# design.net
KiCad netlist of a schematic drawn in Altium Designer
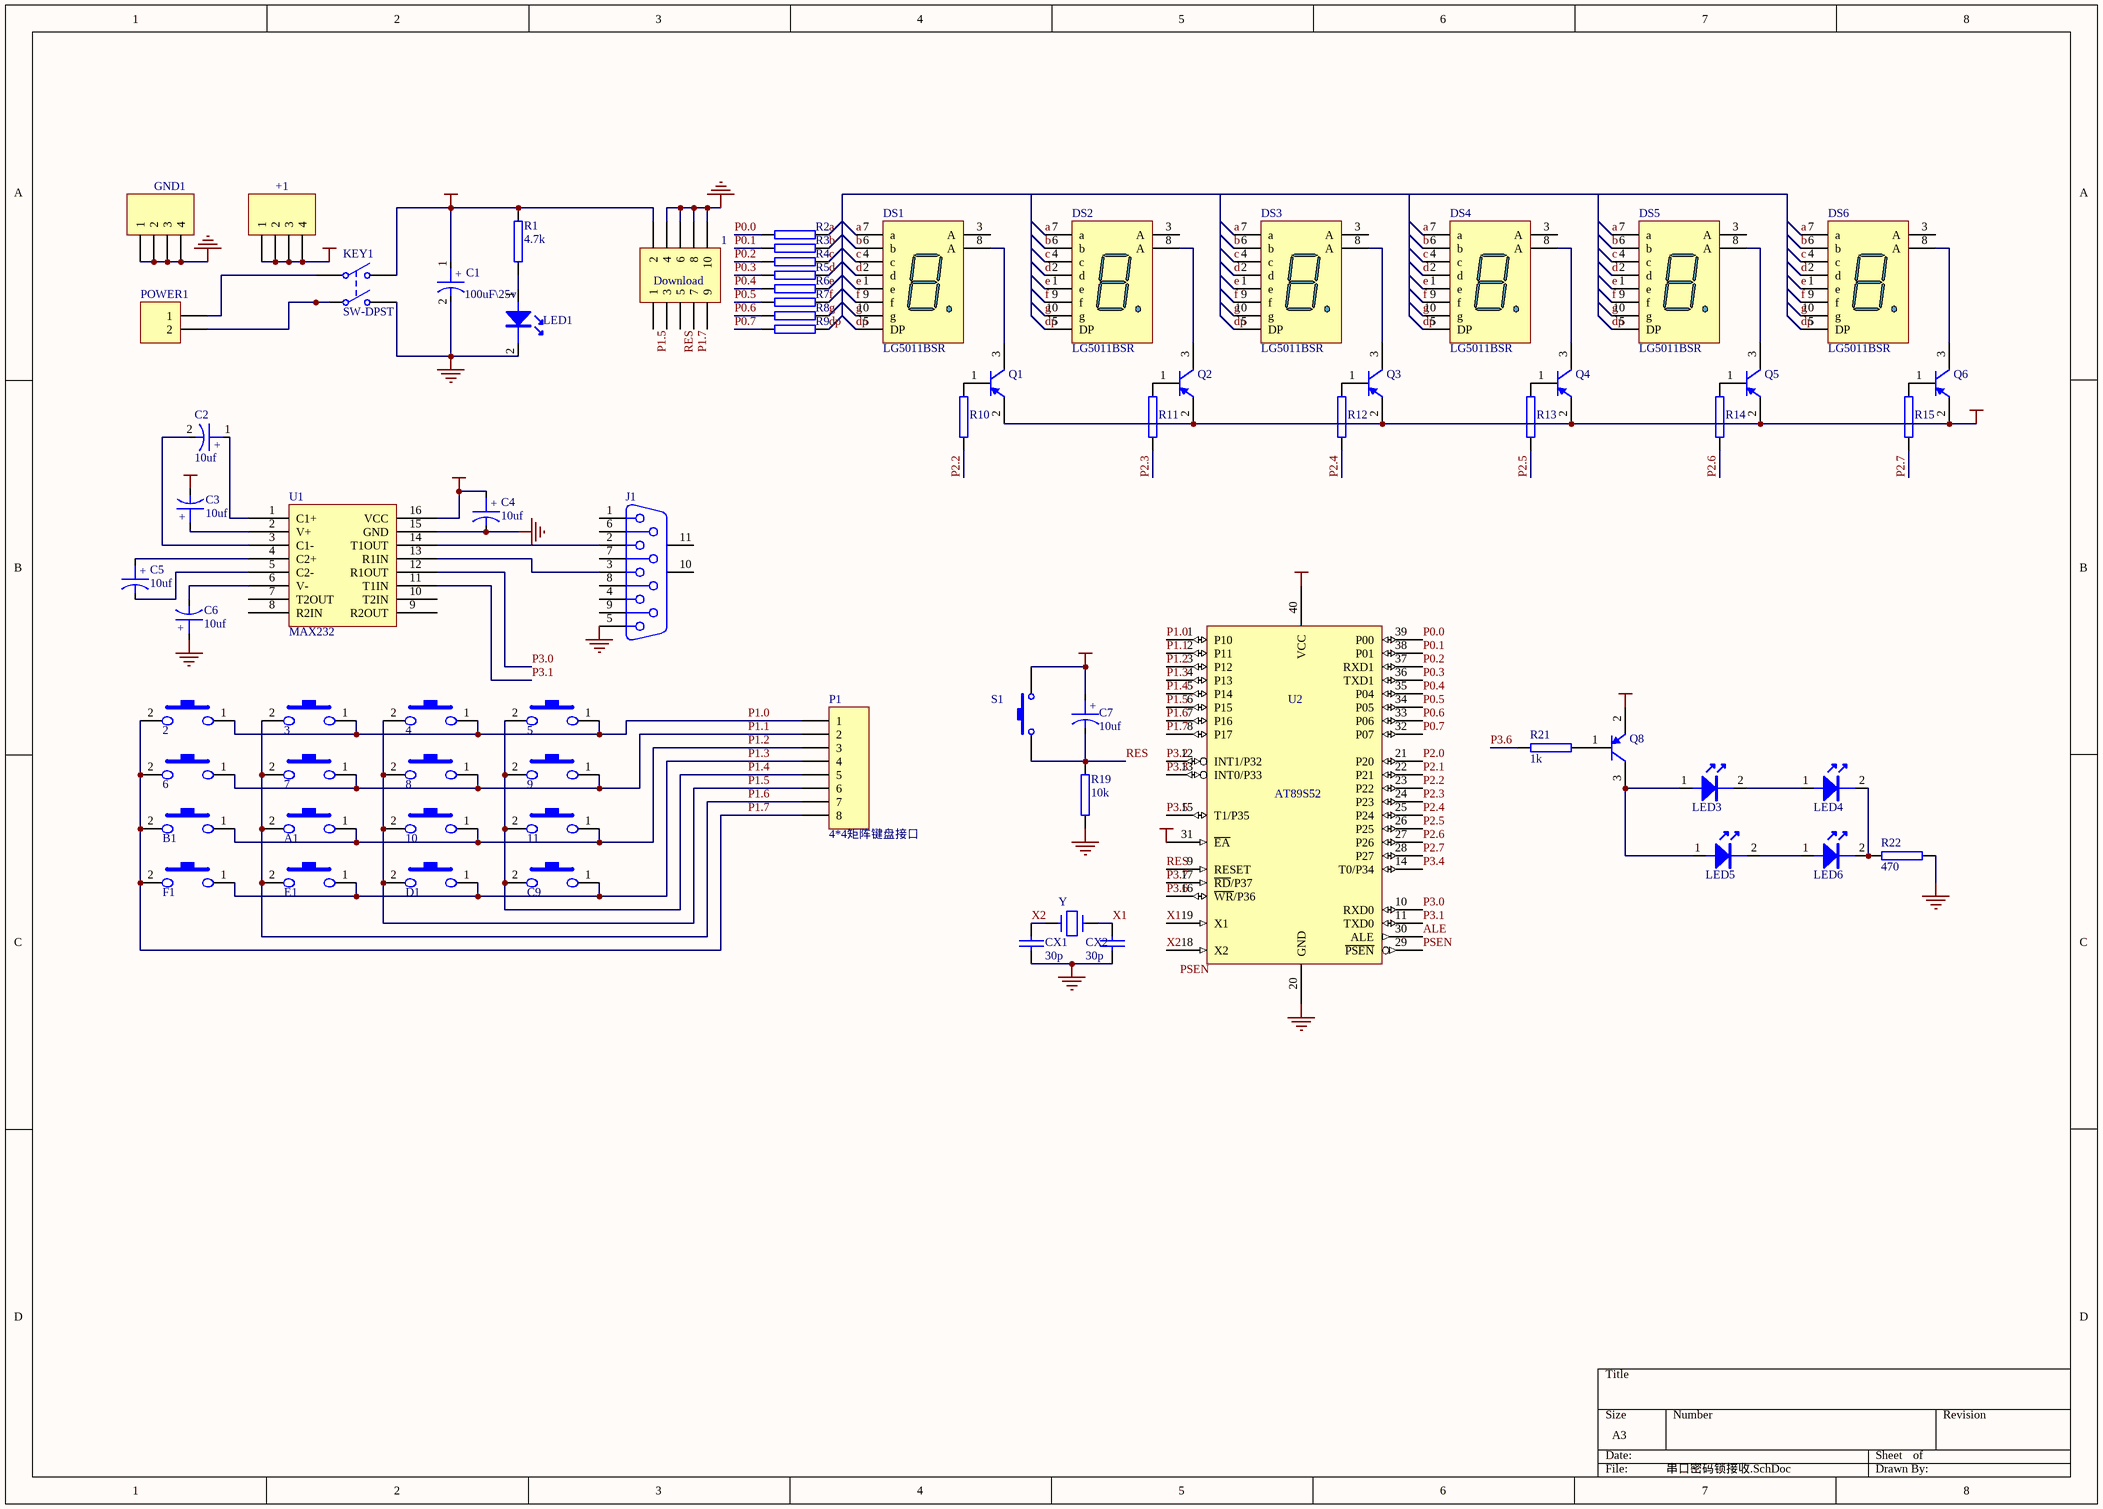
[diagram p0: 串口密码锁接收.SchDoc]

(export (version "E")
  (design (tool "Eeschema 10.0.6"))
  (components
    (comp (ref "+1")
      (value "~")
      (footprint "HDR1X4")
      (description "Header, 4-Pin")
      (fields (field (name "PUBLISHER") "Altium Limited"))
      (libsource (lib "Miscellaneous Connectors") (part "Header 4"))
    )
    (comp (ref "1")
      (value "Download")
      (footprint "HDR-2x5")
      (description "Header, 5-Pin, Dual row")
      (fields (field (name "PUBLISHER") "Altium Limited"))
      (libsource (lib "Miscellaneous Connectors") (part "Header 5X2"))
    )
    (comp (ref "2") (value "key1") (footprint "an-6*6") (libsource (lib "OldCow1 (1)") (part "key")))
    (comp (ref "3") (value "key1") (footprint "an-6*6") (libsource (lib "OldCow1 (1)") (part "key")))
    (comp (ref "4") (value "key1") (footprint "an-6*6") (libsource (lib "OldCow1 (1)") (part "key")))
    (comp (ref "5") (value "key1") (footprint "an-6*6") (libsource (lib "OldCow1 (1)") (part "key")))
    (comp (ref "6") (value "key2") (footprint "an-6*6") (libsource (lib "OldCow1 (1)") (part "key")))
    (comp (ref "7") (value "key2") (footprint "an-6*6") (libsource (lib "OldCow1 (1)") (part "key")))
    (comp (ref "8") (value "key2") (footprint "an-6*6") (libsource (lib "OldCow1 (1)") (part "key")))
    (comp (ref "9") (value "key2") (footprint "an-6*6") (libsource (lib "OldCow1 (1)") (part "key")))
    (comp (ref "10") (value "key3") (footprint "an-6*6") (libsource (lib "OldCow1 (1)") (part "key")))
    (comp (ref "11") (value "key3") (footprint "an-6*6") (libsource (lib "OldCow1 (1)") (part "key")))
    (comp (ref "A1") (value "key3") (footprint "an-6*6") (libsource (lib "OldCow1 (1)") (part "key")))
    (comp (ref "B1") (value "key3") (footprint "an-6*6") (libsource (lib "OldCow1 (1)") (part "key")))
    (comp (ref "C1")
      (value "100u~{F}25v")
      (footprint "C-DJ-6")
      (description "Capacitor")
      (libsource (lib "OldCow1 (1)") (part "CAPACITOR POL"))
    )
    (comp (ref "C2")
      (value "10uf")
      (footprint "C-DJ-4")
      (description "Capacitor")
      (libsource (lib "*") (part "CAPACITOR POL"))
    )
    (comp (ref "C3")
      (value "10uf")
      (footprint "C-DJ-4")
      (description "Capacitor")
      (libsource (lib "") (part "CAPACITOR POL_1"))
    )
    (comp (ref "C4")
      (value "10uf")
      (footprint "C-DJ-4")
      (description "Capacitor")
      (libsource (lib "") (part "CAPACITOR POL_1"))
    )
    (comp (ref "C5")
      (value "10uf")
      (footprint "C-DJ-4")
      (description "Capacitor")
      (libsource (lib "") (part "CAPACITOR POL_1"))
    )
    (comp (ref "C6")
      (value "10uf")
      (footprint "C-DJ-4")
      (description "Capacitor")
      (libsource (lib "") (part "CAPACITOR POL_1"))
    )
    (comp (ref "C7")
      (value "10uf")
      (footprint "C-DJ-4")
      (description "Capacitor")
      (libsource (lib "") (part "CAPACITOR POL_1"))
    )
    (comp (ref "C9") (value "key4") (footprint "an-6*6") (libsource (lib "OldCow1 (1)") (part "key")))
    (comp (ref "CX1")
      (value "30p")
      (footprint "HDR1X2")
      (description "Capacitor")
      (libsource (lib "*") (part "CAP"))
    )
    (comp (ref "CX2")
      (value "30p")
      (footprint "HDR1X2")
      (description "Capacitor")
      (libsource (lib "*") (part "CAP"))
    )
    (comp (ref "D1") (value "key4") (footprint "an-6*6") (libsource (lib "OldCow1 (1)") (part "key")))
    (comp (ref "DS1")
      (value "LG5011BSR")
      (footprint "LED-BSR")
      (description "14.2 mm General Purpose Blue 7-Segment Display: CA, RH DP, Gray Surface")
      (fields (field (name "PUBLISHER") "Altium Limited"))
      (libsource (lib "Miscellaneous Devices") (part "Dpy Blue-CA"))
    )
    (comp (ref "DS2")
      (value "LG5011BSR")
      (footprint "LED-BSR")
      (description "14.2 mm General Purpose Blue 7-Segment Display: CA, RH DP, Gray Surface")
      (fields (field (name "PUBLISHER") "Altium Limited"))
      (libsource (lib "Miscellaneous Devices") (part "Dpy Blue-CA"))
    )
    (comp (ref "DS3")
      (value "LG5011BSR")
      (footprint "LED-BSR")
      (description "14.2 mm General Purpose Blue 7-Segment Display: CA, RH DP, Gray Surface")
      (fields (field (name "PUBLISHER") "Altium Limited"))
      (libsource (lib "Miscellaneous Devices") (part "Dpy Blue-CA"))
    )
    (comp (ref "DS4")
      (value "LG5011BSR")
      (footprint "LED-BSR")
      (description "14.2 mm General Purpose Blue 7-Segment Display: CA, RH DP, Gray Surface")
      (fields (field (name "PUBLISHER") "Altium Limited"))
      (libsource (lib "Miscellaneous Devices") (part "Dpy Blue-CA"))
    )
    (comp (ref "DS5")
      (value "LG5011BSR")
      (footprint "LED-BSR")
      (description "14.2 mm General Purpose Blue 7-Segment Display: CA, RH DP, Gray Surface")
      (fields (field (name "PUBLISHER") "Altium Limited"))
      (libsource (lib "Miscellaneous Devices") (part "Dpy Blue-CA"))
    )
    (comp (ref "DS6")
      (value "LG5011BSR")
      (footprint "LED-BSR")
      (description "14.2 mm General Purpose Blue 7-Segment Display: CA, RH DP, Gray Surface")
      (fields (field (name "PUBLISHER") "Altium Limited"))
      (libsource (lib "Miscellaneous Devices") (part "Dpy Blue-CA"))
    )
    (comp (ref "E1") (value "key4") (footprint "an-6*6") (libsource (lib "OldCow1 (1)") (part "key")))
    (comp (ref "F1") (value "key4") (footprint "an-6*6") (libsource (lib "OldCow1 (1)") (part "key")))
    (comp (ref "GND1")
      (value "~")
      (footprint "HDR1X4")
      (description "Header, 4-Pin")
      (fields (field (name "PUBLISHER") "Altium Limited"))
      (libsource (lib "Miscellaneous Connectors") (part "Header 4"))
    )
    (comp (ref "J1")
      (value "D Connector 9")
      (footprint "DSUB1.385-2H9")
      (description "Receptacle Assembly, 9 Position, Right Angle")
      (fields (field (name "PUBLISHER") "Altium Limited"))
      (libsource (lib "Miscellaneous Connectors") (part "D Connector 9"))
    )
    (comp (ref "KEY1")
      (value "SW-DPST")
      (footprint "DPDT-6")
      (description "Double-Pole, Single-Throw Switch")
      (fields (field (name "PUBLISHER") "Altium Limited"))
      (libsource (lib "Miscellaneous Devices") (part "SW-DPST"))
    )
    (comp (ref "LED1") (value "LED") (footprint "LED") (libsource (lib "OldCow1 (1)") (part "LED")))
    (comp (ref "LED3") (value "LED") (footprint "LED") (libsource (lib "OldCow1 (1)") (part "LED")))
    (comp (ref "LED4") (value "LED") (footprint "LED") (libsource (lib "OldCow1 (1)") (part "LED")))
    (comp (ref "LED5") (value "LED") (footprint "LED") (libsource (lib "OldCow1 (1)") (part "LED")))
    (comp (ref "LED6") (value "LED") (footprint "LED") (libsource (lib "OldCow1 (1)") (part "LED")))
    (comp (ref "P1")
      (value "4*4矩阵键盘接口")
      (footprint "HDR1X8")
      (description "Header, 8-Pin")
      (fields (field (name "PUBLISHER") "Altium Limited"))
      (libsource (lib "Miscellaneous Connectors") (part "Header 8"))
    )
    (comp (ref "POWER1")
      (value "~")
      (footprint "JK128")
      (description "Header, 2-Pin")
      (fields (field (name "PUBLISHER") "Altium Limited"))
      (libsource (lib "Miscellaneous Connectors") (part "Header 2"))
    )
    (comp (ref "Q1")
      (value "2N3906")
      (footprint "SO-G3")
      (description "PNP General Purpose Amplifier")
      (fields (field (name "PUBLISHER") "Altium Limited"))
      (libsource (lib "Miscellaneous Devices") (part "2N3906"))
    )
    (comp (ref "Q2")
      (value "2N3906")
      (footprint "SO-G3")
      (description "PNP General Purpose Amplifier")
      (fields (field (name "PUBLISHER") "Altium Limited"))
      (libsource (lib "Miscellaneous Devices") (part "2N3906"))
    )
    (comp (ref "Q3")
      (value "2N3906")
      (footprint "SO-G3")
      (description "PNP General Purpose Amplifier")
      (fields (field (name "PUBLISHER") "Altium Limited"))
      (libsource (lib "Miscellaneous Devices") (part "2N3906"))
    )
    (comp (ref "Q4")
      (value "2N3906")
      (footprint "SO-G3")
      (description "PNP General Purpose Amplifier")
      (fields (field (name "PUBLISHER") "Altium Limited"))
      (libsource (lib "Miscellaneous Devices") (part "2N3906"))
    )
    (comp (ref "Q5")
      (value "2N3906")
      (footprint "SO-G3")
      (description "PNP General Purpose Amplifier")
      (fields (field (name "PUBLISHER") "Altium Limited"))
      (libsource (lib "Miscellaneous Devices") (part "2N3906"))
    )
    (comp (ref "Q6")
      (value "2N3906")
      (footprint "SO-G3")
      (description "PNP General Purpose Amplifier")
      (fields (field (name "PUBLISHER") "Altium Limited"))
      (libsource (lib "Miscellaneous Devices") (part "2N3906"))
    )
    (comp (ref "Q8")
      (value "2N3906")
      (footprint "SO-G3")
      (description "PNP General Purpose Amplifier")
      (fields (field (name "PUBLISHER") "Altium Limited"))
      (libsource (lib "Miscellaneous Devices") (part "2N3906"))
    )
    (comp (ref "R1") (value "4.7k") (footprint "R2012-0805") (libsource (lib "*") (part "RES2")))
    (comp (ref "R2") (value "470") (footprint "R2012-0805") (libsource (lib "*") (part "RES2")))
    (comp (ref "R3") (value "470") (footprint "R2012-0805") (libsource (lib "*") (part "RES2")))
    (comp (ref "R4") (value "470") (footprint "R2012-0805") (libsource (lib "*") (part "RES2")))
    (comp (ref "R5") (value "470") (footprint "R2012-0805") (libsource (lib "*") (part "RES2")))
    (comp (ref "R6") (value "470") (footprint "R2012-0805") (libsource (lib "*") (part "RES2")))
    (comp (ref "R7") (value "470") (footprint "R2012-0805") (libsource (lib "*") (part "RES2")))
    (comp (ref "R8") (value "470") (footprint "R2012-0805") (libsource (lib "*") (part "RES2")))
    (comp (ref "R9") (value "470") (footprint "R2012-0805") (libsource (lib "*") (part "RES2")))
    (comp (ref "R10") (value "470") (footprint "R2012-0805") (libsource (lib "*") (part "RES2")))
    (comp (ref "R11") (value "470") (footprint "R2012-0805") (libsource (lib "*") (part "RES2")))
    (comp (ref "R12") (value "470") (footprint "R2012-0805") (libsource (lib "*") (part "RES2")))
    (comp (ref "R13") (value "470") (footprint "R2012-0805") (libsource (lib "*") (part "RES2")))
    (comp (ref "R14") (value "470") (footprint "R2012-0805") (libsource (lib "*") (part "RES2")))
    (comp (ref "R15") (value "470") (footprint "R2012-0805") (libsource (lib "*") (part "RES2")))
    (comp (ref "R19") (value "10k") (footprint "R2012-0805") (libsource (lib "*") (part "RES2")))
    (comp (ref "R21") (value "1k") (footprint "R2012-0805") (libsource (lib "*") (part "RES2")))
    (comp (ref "R22") (value "470") (footprint "R2012-0805") (libsource (lib "*") (part "RES2")))
    (comp (ref "S1")
      (value "~")
      (footprint "an-6*6")
      (description "Switch")
      (fields (field (name "PUBLISHER") "Altium Limited"))
      (libsource (lib "Miscellaneous Devices") (part "SW-PB"))
    )
    (comp (ref "U1") (value "MAX232") (footprint "DIP16") (libsource (lib "*") (part "MAX232")))
    (comp (ref "U2") (value "AT89S52") (footprint "AT89S52Pid") (libsource (lib "OldCow1 (2)") (part "8051")))
    (comp (ref "Y1")
      (value "Y")
      (footprint "11.0592M")
      (description "Crystal")
      (libsource (lib "*") (part "CRYSTAL"))
    )
  )
  (nets
    (net (code "1") (name "/ALE") (class "Default")
      (node (ref "U2") (pin "30") (pinfunction "ALE_30") (pintype "output"))
    )
    (net (code "2") (name "/P0.0") (class "Default")
      (node (ref "R2") (pin "1") (pinfunction "1_1") (pintype "passive"))
      (node (ref "U2") (pin "39") (pinfunction "P00_39") (pintype "bidirectional"))
    )
    (net (code "3") (name "/P0.1") (class "Default")
      (node (ref "R3") (pin "1") (pinfunction "1_1") (pintype "passive"))
      (node (ref "U2") (pin "38") (pinfunction "P01_38") (pintype "bidirectional"))
    )
    (net (code "4") (name "/P0.2") (class "Default")
      (node (ref "R4") (pin "1") (pinfunction "1_1") (pintype "passive"))
      (node (ref "U2") (pin "37") (pinfunction "RXD1_37") (pintype "bidirectional"))
    )
    (net (code "5") (name "/P0.3") (class "Default")
      (node (ref "R5") (pin "1") (pinfunction "1_1") (pintype "passive"))
      (node (ref "U2") (pin "36") (pinfunction "TXD1_36") (pintype "bidirectional"))
    )
    (net (code "6") (name "/P0.4") (class "Default")
      (node (ref "R6") (pin "1") (pinfunction "1_1") (pintype "passive"))
      (node (ref "U2") (pin "35") (pinfunction "P04_35") (pintype "bidirectional"))
    )
    (net (code "7") (name "/P0.5") (class "Default")
      (node (ref "R7") (pin "1") (pinfunction "1_1") (pintype "passive"))
      (node (ref "U2") (pin "34") (pinfunction "P05_34") (pintype "bidirectional"))
    )
    (net (code "8") (name "/P0.6") (class "Default")
      (node (ref "R8") (pin "1") (pinfunction "1_1") (pintype "passive"))
      (node (ref "U2") (pin "33") (pinfunction "P06_33") (pintype "bidirectional"))
    )
    (net (code "9") (name "/P0.7") (class "Default")
      (node (ref "R9") (pin "1") (pinfunction "1_1") (pintype "passive"))
      (node (ref "U2") (pin "32") (pinfunction "P07_32") (pintype "bidirectional"))
    )
    (net (code "10") (name "/P1.0") (class "Default")
      (node (ref "2") (pin "1") (pinfunction "1_1") (pintype "passive"))
      (node (ref "3") (pin "1") (pinfunction "1_1") (pintype "passive"))
      (node (ref "4") (pin "1") (pinfunction "1_1") (pintype "passive"))
      (node (ref "5") (pin "1") (pinfunction "1_1") (pintype "passive"))
      (node (ref "P1") (pin "1") (pinfunction "1_1") (pintype "passive"))
      (node (ref "U2") (pin "1") (pinfunction "P10_1") (pintype "bidirectional"))
    )
    (net (code "11") (name "/P1.1") (class "Default")
      (node (ref "6") (pin "1") (pinfunction "1_1") (pintype "passive"))
      (node (ref "7") (pin "1") (pinfunction "1_1") (pintype "passive"))
      (node (ref "8") (pin "1") (pinfunction "1_1") (pintype "passive"))
      (node (ref "9") (pin "1") (pinfunction "1_1") (pintype "passive"))
      (node (ref "P1") (pin "2") (pinfunction "2_2") (pintype "passive"))
      (node (ref "U2") (pin "2") (pinfunction "P11_2") (pintype "bidirectional"))
    )
    (net (code "12") (name "/P1.2") (class "Default")
      (node (ref "10") (pin "1") (pinfunction "1_1") (pintype "passive"))
      (node (ref "11") (pin "1") (pinfunction "1_1") (pintype "passive"))
      (node (ref "A1") (pin "1") (pinfunction "1_1") (pintype "passive"))
      (node (ref "B1") (pin "1") (pinfunction "1_1") (pintype "passive"))
      (node (ref "P1") (pin "3") (pinfunction "3_3") (pintype "passive"))
      (node (ref "U2") (pin "3") (pinfunction "P12_3") (pintype "bidirectional"))
    )
    (net (code "13") (name "/P1.3") (class "Default")
      (node (ref "C9") (pin "1") (pinfunction "1_1") (pintype "passive"))
      (node (ref "D1") (pin "1") (pinfunction "1_1") (pintype "passive"))
      (node (ref "E1") (pin "1") (pinfunction "1_1") (pintype "passive"))
      (node (ref "F1") (pin "1") (pinfunction "1_1") (pintype "passive"))
      (node (ref "P1") (pin "4") (pinfunction "4_4") (pintype "passive"))
      (node (ref "U2") (pin "4") (pinfunction "P13_4") (pintype "bidirectional"))
    )
    (net (code "14") (name "/P1.4") (class "Default")
      (node (ref "11") (pin "2") (pinfunction "2_2") (pintype "passive"))
      (node (ref "5") (pin "2") (pinfunction "2_2") (pintype "passive"))
      (node (ref "9") (pin "2") (pinfunction "2_2") (pintype "passive"))
      (node (ref "C9") (pin "2") (pinfunction "2_2") (pintype "passive"))
      (node (ref "P1") (pin "5") (pinfunction "5_5") (pintype "passive"))
      (node (ref "U2") (pin "5") (pinfunction "P14_5") (pintype "bidirectional"))
    )
    (net (code "15") (name "/P1.5") (class "Default")
      (node (ref "1") (pin "1") (pinfunction "1_1") (pintype "passive"))
      (node (ref "10") (pin "2") (pinfunction "2_2") (pintype "passive"))
      (node (ref "4") (pin "2") (pinfunction "2_2") (pintype "passive"))
      (node (ref "8") (pin "2") (pinfunction "2_2") (pintype "passive"))
      (node (ref "D1") (pin "2") (pinfunction "2_2") (pintype "passive"))
      (node (ref "P1") (pin "6") (pinfunction "6_6") (pintype "passive"))
      (node (ref "U2") (pin "6") (pinfunction "P15_6") (pintype "bidirectional"))
    )
    (net (code "16") (name "/P1.6") (class "Default")
      (node (ref "3") (pin "2") (pinfunction "2_2") (pintype "passive"))
      (node (ref "7") (pin "2") (pinfunction "2_2") (pintype "passive"))
      (node (ref "A1") (pin "2") (pinfunction "2_2") (pintype "passive"))
      (node (ref "E1") (pin "2") (pinfunction "2_2") (pintype "passive"))
      (node (ref "P1") (pin "7") (pinfunction "7_7") (pintype "passive"))
      (node (ref "U2") (pin "7") (pinfunction "P16_7") (pintype "bidirectional"))
    )
    (net (code "17") (name "/P1.7") (class "Default")
      (node (ref "1") (pin "7") (pinfunction "7_7") (pintype "passive"))
      (node (ref "2") (pin "2") (pinfunction "2_2") (pintype "passive"))
      (node (ref "6") (pin "2") (pinfunction "2_2") (pintype "passive"))
      (node (ref "B1") (pin "2") (pinfunction "2_2") (pintype "passive"))
      (node (ref "F1") (pin "2") (pinfunction "2_2") (pintype "passive"))
      (node (ref "P1") (pin "8") (pinfunction "8_8") (pintype "passive"))
      (node (ref "U2") (pin "8") (pinfunction "P17_8") (pintype "bidirectional"))
    )
    (net (code "18") (name "/P2.0") (class "Default")
      (node (ref "U2") (pin "21") (pinfunction "P20_21") (pintype "bidirectional"))
    )
    (net (code "19") (name "/P2.1") (class "Default")
      (node (ref "U2") (pin "22") (pinfunction "P21_22") (pintype "bidirectional"))
    )
    (net (code "20") (name "/P2.2") (class "Default")
      (node (ref "R10") (pin "1") (pinfunction "1_1") (pintype "passive"))
      (node (ref "U2") (pin "23") (pinfunction "P22_23") (pintype "bidirectional"))
    )
    (net (code "21") (name "/P2.3") (class "Default")
      (node (ref "R11") (pin "1") (pinfunction "1_1") (pintype "passive"))
      (node (ref "U2") (pin "24") (pinfunction "P23_24") (pintype "bidirectional"))
    )
    (net (code "22") (name "/P2.4") (class "Default")
      (node (ref "R12") (pin "1") (pinfunction "1_1") (pintype "passive"))
      (node (ref "U2") (pin "25") (pinfunction "P24_25") (pintype "bidirectional"))
    )
    (net (code "23") (name "/P2.5") (class "Default")
      (node (ref "R13") (pin "1") (pinfunction "1_1") (pintype "passive"))
      (node (ref "U2") (pin "26") (pinfunction "P25_26") (pintype "bidirectional"))
    )
    (net (code "24") (name "/P2.6") (class "Default")
      (node (ref "R14") (pin "1") (pinfunction "1_1") (pintype "passive"))
      (node (ref "U2") (pin "27") (pinfunction "P26_27") (pintype "bidirectional"))
    )
    (net (code "25") (name "/P2.7") (class "Default")
      (node (ref "R15") (pin "1") (pinfunction "1_1") (pintype "passive"))
      (node (ref "U2") (pin "28") (pinfunction "P27_28") (pintype "bidirectional"))
    )
    (net (code "26") (name "/P3.0") (class "Default")
      (node (ref "U1") (pin "12") (pinfunction "R1OUT_12") (pintype "passive"))
      (node (ref "U2") (pin "10") (pinfunction "RXD0_10") (pintype "bidirectional"))
    )
    (net (code "27") (name "/P3.1") (class "Default")
      (node (ref "U1") (pin "11") (pinfunction "T1IN_11") (pintype "passive"))
      (node (ref "U2") (pin "11") (pinfunction "TXD0_11") (pintype "bidirectional"))
    )
    (net (code "28") (name "/P3.2") (class "Default")
      (node (ref "U2") (pin "12") (pinfunction "INT1/P32_12") (pintype "bidirectional"))
    )
    (net (code "29") (name "/P3.3") (class "Default")
      (node (ref "U2") (pin "13") (pinfunction "INT0/P33_13") (pintype "bidirectional"))
    )
    (net (code "30") (name "/P3.4") (class "Default")
      (node (ref "U2") (pin "14") (pinfunction "T0/P34_14") (pintype "bidirectional"))
    )
    (net (code "31") (name "/P3.5") (class "Default")
      (node (ref "U2") (pin "15") (pinfunction "T1/P35_15") (pintype "bidirectional"))
    )
    (net (code "32") (name "/P3.6") (class "Default")
      (node (ref "R21") (pin "1") (pinfunction "1_1") (pintype "passive"))
      (node (ref "U2") (pin "16") (pinfunction "~{WR}/P36_16") (pintype "bidirectional"))
    )
    (net (code "33") (name "/P3.7") (class "Default")
      (node (ref "U2") (pin "17") (pinfunction "~{RD}/P37_17") (pintype "input"))
    )
    (net (code "34") (name "/PSEN") (class "Default")
      (node (ref "U2") (pin "29") (pinfunction "~{PSEN}_29") (pintype "output"))
    )
    (net (code "35") (name "/RES") (class "Default")
      (node (ref "1") (pin "5") (pinfunction "5_5") (pintype "passive"))
      (node (ref "C7") (pin "2") (pinfunction "2_2") (pintype "passive"))
      (node (ref "R19") (pin "1") (pinfunction "1_1") (pintype "passive"))
      (node (ref "S1") (pin "1") (pinfunction "1_1") (pintype "passive"))
      (node (ref "U2") (pin "9") (pinfunction "RESET_9") (pintype "input"))
    )
    (net (code "36") (name "/X1") (class "Default")
      (node (ref "CX2") (pin "1") (pinfunction "1_1") (pintype "passive"))
      (node (ref "U2") (pin "19") (pinfunction "X1_19") (pintype "input"))
      (node (ref "Y1") (pin "1") (pinfunction "1_1") (pintype "passive"))
    )
    (net (code "37") (name "/X2") (class "Default")
      (node (ref "CX1") (pin "1") (pinfunction "1_1") (pintype "passive"))
      (node (ref "U2") (pin "18") (pinfunction "X2_18") (pintype "input"))
      (node (ref "Y1") (pin "2") (pinfunction "2_2") (pintype "passive"))
    )
    (net (code "38") (name "/a") (class "Default")
      (node (ref "DS1") (pin "7") (pinfunction "a_7") (pintype "passive"))
      (node (ref "DS2") (pin "7") (pinfunction "a_7") (pintype "passive"))
      (node (ref "DS3") (pin "7") (pinfunction "a_7") (pintype "passive"))
      (node (ref "DS4") (pin "7") (pinfunction "a_7") (pintype "passive"))
      (node (ref "DS5") (pin "7") (pinfunction "a_7") (pintype "passive"))
      (node (ref "DS6") (pin "7") (pinfunction "a_7") (pintype "passive"))
      (node (ref "R2") (pin "2") (pinfunction "2_2") (pintype "passive"))
    )
    (net (code "39") (name "/b") (class "Default")
      (node (ref "DS1") (pin "6") (pinfunction "b_6") (pintype "passive"))
      (node (ref "DS2") (pin "6") (pinfunction "b_6") (pintype "passive"))
      (node (ref "DS3") (pin "6") (pinfunction "b_6") (pintype "passive"))
      (node (ref "DS4") (pin "6") (pinfunction "b_6") (pintype "passive"))
      (node (ref "DS5") (pin "6") (pinfunction "b_6") (pintype "passive"))
      (node (ref "DS6") (pin "6") (pinfunction "b_6") (pintype "passive"))
      (node (ref "R3") (pin "2") (pinfunction "2_2") (pintype "passive"))
    )
    (net (code "40") (name "/c") (class "Default")
      (node (ref "DS1") (pin "4") (pinfunction "c_4") (pintype "passive"))
      (node (ref "DS2") (pin "4") (pinfunction "c_4") (pintype "passive"))
      (node (ref "DS3") (pin "4") (pinfunction "c_4") (pintype "passive"))
      (node (ref "DS4") (pin "4") (pinfunction "c_4") (pintype "passive"))
      (node (ref "DS5") (pin "4") (pinfunction "c_4") (pintype "passive"))
      (node (ref "DS6") (pin "4") (pinfunction "c_4") (pintype "passive"))
      (node (ref "R4") (pin "2") (pinfunction "2_2") (pintype "passive"))
    )
    (net (code "41") (name "/d") (class "Default")
      (node (ref "DS1") (pin "2") (pinfunction "d_2") (pintype "passive"))
      (node (ref "DS2") (pin "2") (pinfunction "d_2") (pintype "passive"))
      (node (ref "DS3") (pin "2") (pinfunction "d_2") (pintype "passive"))
      (node (ref "DS4") (pin "2") (pinfunction "d_2") (pintype "passive"))
      (node (ref "DS5") (pin "2") (pinfunction "d_2") (pintype "passive"))
      (node (ref "DS6") (pin "2") (pinfunction "d_2") (pintype "passive"))
      (node (ref "R5") (pin "2") (pinfunction "2_2") (pintype "passive"))
    )
    (net (code "42") (name "/dp") (class "Default")
      (node (ref "DS1") (pin "5") (pinfunction "DP_5") (pintype "passive"))
      (node (ref "DS2") (pin "5") (pinfunction "DP_5") (pintype "passive"))
      (node (ref "DS3") (pin "5") (pinfunction "DP_5") (pintype "passive"))
      (node (ref "DS4") (pin "5") (pinfunction "DP_5") (pintype "passive"))
      (node (ref "DS5") (pin "5") (pinfunction "DP_5") (pintype "passive"))
      (node (ref "DS6") (pin "5") (pinfunction "DP_5") (pintype "passive"))
      (node (ref "R9") (pin "2") (pinfunction "2_2") (pintype "passive"))
    )
    (net (code "43") (name "/e") (class "Default")
      (node (ref "DS1") (pin "1") (pinfunction "e_1") (pintype "passive"))
      (node (ref "DS2") (pin "1") (pinfunction "e_1") (pintype "passive"))
      (node (ref "DS3") (pin "1") (pinfunction "e_1") (pintype "passive"))
      (node (ref "DS4") (pin "1") (pinfunction "e_1") (pintype "passive"))
      (node (ref "DS5") (pin "1") (pinfunction "e_1") (pintype "passive"))
      (node (ref "DS6") (pin "1") (pinfunction "e_1") (pintype "passive"))
      (node (ref "R6") (pin "2") (pinfunction "2_2") (pintype "passive"))
    )
    (net (code "44") (name "/f") (class "Default")
      (node (ref "DS1") (pin "9") (pinfunction "f_9") (pintype "passive"))
      (node (ref "DS2") (pin "9") (pinfunction "f_9") (pintype "passive"))
      (node (ref "DS3") (pin "9") (pinfunction "f_9") (pintype "passive"))
      (node (ref "DS4") (pin "9") (pinfunction "f_9") (pintype "passive"))
      (node (ref "DS5") (pin "9") (pinfunction "f_9") (pintype "passive"))
      (node (ref "DS6") (pin "9") (pinfunction "f_9") (pintype "passive"))
      (node (ref "R7") (pin "2") (pinfunction "2_2") (pintype "passive"))
    )
    (net (code "45") (name "/g") (class "Default")
      (node (ref "DS1") (pin "10") (pinfunction "g_10") (pintype "passive"))
      (node (ref "DS2") (pin "10") (pinfunction "g_10") (pintype "passive"))
      (node (ref "DS3") (pin "10") (pinfunction "g_10") (pintype "passive"))
      (node (ref "DS4") (pin "10") (pinfunction "g_10") (pintype "passive"))
      (node (ref "DS5") (pin "10") (pinfunction "g_10") (pintype "passive"))
      (node (ref "DS6") (pin "10") (pinfunction "g_10") (pintype "passive"))
      (node (ref "R8") (pin "2") (pinfunction "2_2") (pintype "passive"))
    )
    (net (code "46") (name "GND") (class "Default")
      (node (ref "1") (pin "10") (pinfunction "10_10") (pintype "passive"))
      (node (ref "1") (pin "4") (pinfunction "4_4") (pintype "passive"))
      (node (ref "1") (pin "6") (pinfunction "6_6") (pintype "passive"))
      (node (ref "1") (pin "8") (pinfunction "8_8") (pintype "passive"))
      (node (ref "C1") (pin "2") (pinfunction "2_2") (pintype "passive"))
      (node (ref "C4") (pin "2") (pinfunction "2_2") (pintype "passive"))
      (node (ref "C6") (pin "1") (pinfunction "1_1") (pintype "passive"))
      (node (ref "CX1") (pin "2") (pinfunction "2_2") (pintype "passive"))
      (node (ref "CX2") (pin "2") (pinfunction "2_2") (pintype "passive"))
      (node (ref "GND1") (pin "1") (pinfunction "1_1") (pintype "passive"))
      (node (ref "GND1") (pin "2") (pinfunction "2_2") (pintype "passive"))
      (node (ref "GND1") (pin "3") (pinfunction "3_3") (pintype "passive"))
      (node (ref "GND1") (pin "4") (pinfunction "4_4") (pintype "passive"))
      (node (ref "J1") (pin "5") (pinfunction "5_5") (pintype "passive"))
      (node (ref "KEY1") (pin "4") (pinfunction "NO2_4") (pintype "passive"))
      (node (ref "LED1") (pin "2") (pinfunction "K_2") (pintype "passive"))
      (node (ref "R19") (pin "2") (pinfunction "2_2") (pintype "passive"))
      (node (ref "R22") (pin "2") (pinfunction "2_2") (pintype "passive"))
      (node (ref "U1") (pin "15") (pinfunction "GND_15") (pintype "passive"))
      (node (ref "U2") (pin "20") (pinfunction "GND_20") (pintype "power_in"))
    )
    (net (code "47") (name "Net-(KEY1-COMMON1)") (class "Default")
      (node (ref "KEY1") (pin "1") (pinfunction "COMMON1_1") (pintype "passive"))
      (node (ref "POWER1") (pin "1") (pinfunction "1_1") (pintype "passive"))
    )
    (net (code "48") (name "Net-(KEY1-COMMON2)") (class "Default")
      (node (ref "KEY1") (pin "3") (pinfunction "COMMON2_3") (pintype "passive"))
      (node (ref "POWER1") (pin "2") (pinfunction "2_2") (pintype "passive"))
    )
    (net (code "49") (name "Net-(LED1-A)") (class "Default")
      (node (ref "LED1") (pin "1") (pinfunction "A_1") (pintype "passive"))
      (node (ref "R1") (pin "2") (pinfunction "2_2") (pintype "passive"))
    )
    (net (code "50") (name "Net-(LED3-A)") (class "Default")
      (node (ref "LED3") (pin "1") (pinfunction "A_1") (pintype "passive"))
      (node (ref "LED5") (pin "1") (pinfunction "A_1") (pintype "passive"))
      (node (ref "Q8") (pin "3") (pinfunction "C_3") (pintype "passive"))
    )
    (net (code "51") (name "Net-(LED3-K)") (class "Default")
      (node (ref "LED3") (pin "2") (pinfunction "K_2") (pintype "passive"))
      (node (ref "LED4") (pin "1") (pinfunction "A_1") (pintype "passive"))
    )
    (net (code "52") (name "Net-(LED4-K)") (class "Default")
      (node (ref "LED4") (pin "2") (pinfunction "K_2") (pintype "passive"))
      (node (ref "LED6") (pin "2") (pinfunction "K_2") (pintype "passive"))
      (node (ref "R22") (pin "1") (pinfunction "1_1") (pintype "passive"))
    )
    (net (code "53") (name "Net-(LED5-K)") (class "Default")
      (node (ref "LED5") (pin "2") (pinfunction "K_2") (pintype "passive"))
      (node (ref "LED6") (pin "1") (pinfunction "A_1") (pintype "passive"))
    )
    (net (code "54") (name "Net-(Q1-B)") (class "Default")
      (node (ref "Q1") (pin "1") (pinfunction "B_1") (pintype "passive"))
      (node (ref "R10") (pin "2") (pinfunction "2_2") (pintype "passive"))
    )
    (net (code "55") (name "Net-(Q1-C)") (class "Default")
      (node (ref "DS1") (pin "8") (pinfunction "A_8") (pintype "passive"))
      (node (ref "Q1") (pin "3") (pinfunction "C_3") (pintype "passive"))
    )
    (net (code "56") (name "Net-(Q2-B)") (class "Default")
      (node (ref "Q2") (pin "1") (pinfunction "B_1") (pintype "passive"))
      (node (ref "R11") (pin "2") (pinfunction "2_2") (pintype "passive"))
    )
    (net (code "57") (name "Net-(Q2-C)") (class "Default")
      (node (ref "DS2") (pin "8") (pinfunction "A_8") (pintype "passive"))
      (node (ref "Q2") (pin "3") (pinfunction "C_3") (pintype "passive"))
    )
    (net (code "58") (name "Net-(Q3-B)") (class "Default")
      (node (ref "Q3") (pin "1") (pinfunction "B_1") (pintype "passive"))
      (node (ref "R12") (pin "2") (pinfunction "2_2") (pintype "passive"))
    )
    (net (code "59") (name "Net-(Q3-C)") (class "Default")
      (node (ref "DS3") (pin "8") (pinfunction "A_8") (pintype "passive"))
      (node (ref "Q3") (pin "3") (pinfunction "C_3") (pintype "passive"))
    )
    (net (code "60") (name "Net-(Q4-B)") (class "Default")
      (node (ref "Q4") (pin "1") (pinfunction "B_1") (pintype "passive"))
      (node (ref "R13") (pin "2") (pinfunction "2_2") (pintype "passive"))
    )
    (net (code "61") (name "Net-(Q4-C)") (class "Default")
      (node (ref "DS4") (pin "8") (pinfunction "A_8") (pintype "passive"))
      (node (ref "Q4") (pin "3") (pinfunction "C_3") (pintype "passive"))
    )
    (net (code "62") (name "Net-(Q5-B)") (class "Default")
      (node (ref "Q5") (pin "1") (pinfunction "B_1") (pintype "passive"))
      (node (ref "R14") (pin "2") (pinfunction "2_2") (pintype "passive"))
    )
    (net (code "63") (name "Net-(Q5-C)") (class "Default")
      (node (ref "DS5") (pin "8") (pinfunction "A_8") (pintype "passive"))
      (node (ref "Q5") (pin "3") (pinfunction "C_3") (pintype "passive"))
    )
    (net (code "64") (name "Net-(Q6-B)") (class "Default")
      (node (ref "Q6") (pin "1") (pinfunction "B_1") (pintype "passive"))
      (node (ref "R15") (pin "2") (pinfunction "2_2") (pintype "passive"))
    )
    (net (code "65") (name "Net-(Q6-C)") (class "Default")
      (node (ref "DS6") (pin "8") (pinfunction "A_8") (pintype "passive"))
      (node (ref "Q6") (pin "3") (pinfunction "C_3") (pintype "passive"))
    )
    (net (code "66") (name "Net-(Q8-B)") (class "Default")
      (node (ref "Q8") (pin "1") (pinfunction "B_1") (pintype "passive"))
      (node (ref "R21") (pin "2") (pinfunction "2_2") (pintype "passive"))
    )
    (net (code "67") (name "Net-(U1-C1+)") (class "Default")
      (node (ref "C2") (pin "1") (pinfunction "1_1") (pintype "passive"))
      (node (ref "U1") (pin "1") (pinfunction "C1+_1") (pintype "passive"))
    )
    (net (code "68") (name "Net-(U1-C1-)") (class "Default")
      (node (ref "C2") (pin "2") (pinfunction "2_2") (pintype "passive"))
      (node (ref "U1") (pin "3") (pinfunction "C1-_3") (pintype "passive"))
    )
    (net (code "69") (name "Net-(U1-C2+)") (class "Default")
      (node (ref "C5") (pin "1") (pinfunction "1_1") (pintype "passive"))
      (node (ref "U1") (pin "4") (pinfunction "C2+_4") (pintype "passive"))
    )
    (net (code "70") (name "Net-(U1-C2-)") (class "Default")
      (node (ref "C5") (pin "2") (pinfunction "2_2") (pintype "passive"))
      (node (ref "U1") (pin "5") (pinfunction "C2-_5") (pintype "passive"))
    )
    (net (code "71") (name "Net-(U1-R1IN)") (class "Default")
      (node (ref "J1") (pin "3") (pinfunction "3_3") (pintype "passive"))
      (node (ref "U1") (pin "13") (pinfunction "R1IN_13") (pintype "passive"))
    )
    (net (code "72") (name "Net-(U1-T1OUT)") (class "Default")
      (node (ref "J1") (pin "2") (pinfunction "2_2") (pintype "passive"))
      (node (ref "U1") (pin "14") (pinfunction "T1OUT_14") (pintype "passive"))
    )
    (net (code "73") (name "Net-(U1-V+)") (class "Default")
      (node (ref "C3") (pin "1") (pinfunction "1_1") (pintype "passive"))
      (node (ref "U1") (pin "2") (pinfunction "V+_2") (pintype "passive"))
    )
    (net (code "74") (name "Net-(U1-V-)") (class "Default")
      (node (ref "C6") (pin "2") (pinfunction "2_2") (pintype "passive"))
      (node (ref "U1") (pin "6") (pinfunction "V-_6") (pintype "passive"))
    )
    (net (code "75") (name "VCC") (class "Default")
      (node (ref "+1") (pin "1") (pinfunction "1_1") (pintype "passive"))
      (node (ref "+1") (pin "2") (pinfunction "2_2") (pintype "passive"))
      (node (ref "+1") (pin "3") (pinfunction "3_3") (pintype "passive"))
      (node (ref "+1") (pin "4") (pinfunction "4_4") (pintype "passive"))
      (node (ref "1") (pin "2") (pinfunction "2_2") (pintype "passive"))
      (node (ref "C1") (pin "1") (pinfunction "1_1") (pintype "passive"))
      (node (ref "C3") (pin "2") (pinfunction "2_2") (pintype "passive"))
      (node (ref "C4") (pin "1") (pinfunction "1_1") (pintype "passive"))
      (node (ref "C7") (pin "1") (pinfunction "1_1") (pintype "passive"))
      (node (ref "KEY1") (pin "2") (pinfunction "NO1_2") (pintype "passive"))
      (node (ref "Q1") (pin "2") (pinfunction "E_2") (pintype "passive"))
      (node (ref "Q2") (pin "2") (pinfunction "E_2") (pintype "passive"))
      (node (ref "Q3") (pin "2") (pinfunction "E_2") (pintype "passive"))
      (node (ref "Q4") (pin "2") (pinfunction "E_2") (pintype "passive"))
      (node (ref "Q5") (pin "2") (pinfunction "E_2") (pintype "passive"))
      (node (ref "Q6") (pin "2") (pinfunction "E_2") (pintype "passive"))
      (node (ref "Q8") (pin "2") (pinfunction "E_2") (pintype "passive"))
      (node (ref "R1") (pin "1") (pinfunction "1_1") (pintype "passive"))
      (node (ref "S1") (pin "2") (pinfunction "2_2") (pintype "passive"))
      (node (ref "U1") (pin "16") (pinfunction "VCC_16") (pintype "passive"))
      (node (ref "U2") (pin "31") (pinfunction "~{EA}_31") (pintype "input"))
      (node (ref "U2") (pin "40") (pinfunction "VCC_40") (pintype "power_in"))
    )
    (net (code "76") (name "unconnected-(1-Pad3)") (class "Default")
      (node (ref "1") (pin "3") (pinfunction "3_3") (pintype "passive"))
    )
    (net (code "77") (name "unconnected-(1-Pad9)") (class "Default")
      (node (ref "1") (pin "9") (pinfunction "9_9") (pintype "passive"))
    )
    (net (code "78") (name "unconnected-(DS1-A-Pad3)") (class "Default")
      (node (ref "DS1") (pin "3") (pinfunction "A_3") (pintype "passive"))
    )
    (net (code "79") (name "unconnected-(DS2-A-Pad3)") (class "Default")
      (node (ref "DS2") (pin "3") (pinfunction "A_3") (pintype "passive"))
    )
    (net (code "80") (name "unconnected-(DS3-A-Pad3)") (class "Default")
      (node (ref "DS3") (pin "3") (pinfunction "A_3") (pintype "passive"))
    )
    (net (code "81") (name "unconnected-(DS4-A-Pad3)") (class "Default")
      (node (ref "DS4") (pin "3") (pinfunction "A_3") (pintype "passive"))
    )
    (net (code "82") (name "unconnected-(DS5-A-Pad3)") (class "Default")
      (node (ref "DS5") (pin "3") (pinfunction "A_3") (pintype "passive"))
    )
    (net (code "83") (name "unconnected-(DS6-A-Pad3)") (class "Default")
      (node (ref "DS6") (pin "3") (pinfunction "A_3") (pintype "passive"))
    )
    (net (code "84") (name "unconnected-(J1-MH1-Pad10)") (class "Default")
      (node (ref "J1") (pin "10") (pinfunction "MH1_10") (pintype "passive"))
    )
    (net (code "85") (name "unconnected-(J1-MH2-Pad11)") (class "Default")
      (node (ref "J1") (pin "11") (pinfunction "MH2_11") (pintype "passive"))
    )
    (net (code "86") (name "unconnected-(J1-Pad1)") (class "Default")
      (node (ref "J1") (pin "1") (pinfunction "1_1") (pintype "passive"))
    )
    (net (code "87") (name "unconnected-(J1-Pad4)") (class "Default")
      (node (ref "J1") (pin "4") (pinfunction "4_4") (pintype "passive"))
    )
    (net (code "88") (name "unconnected-(J1-Pad6)") (class "Default")
      (node (ref "J1") (pin "6") (pinfunction "6_6") (pintype "passive"))
    )
    (net (code "89") (name "unconnected-(J1-Pad7)") (class "Default")
      (node (ref "J1") (pin "7") (pinfunction "7_7") (pintype "passive"))
    )
    (net (code "90") (name "unconnected-(J1-Pad8)") (class "Default")
      (node (ref "J1") (pin "8") (pinfunction "8_8") (pintype "passive"))
    )
    (net (code "91") (name "unconnected-(J1-Pad9)") (class "Default")
      (node (ref "J1") (pin "9") (pinfunction "9_9") (pintype "passive"))
    )
    (net (code "92") (name "unconnected-(U1-R2IN-Pad8)") (class "Default")
      (node (ref "U1") (pin "8") (pinfunction "R2IN_8") (pintype "passive"))
    )
    (net (code "93") (name "unconnected-(U1-R2OUT-Pad9)") (class "Default")
      (node (ref "U1") (pin "9") (pinfunction "R2OUT_9") (pintype "passive"))
    )
    (net (code "94") (name "unconnected-(U1-T2IN-Pad10)") (class "Default")
      (node (ref "U1") (pin "10") (pinfunction "T2IN_10") (pintype "passive"))
    )
    (net (code "95") (name "unconnected-(U1-T2OUT-Pad7)") (class "Default")
      (node (ref "U1") (pin "7") (pinfunction "T2OUT_7") (pintype "passive"))
    )
  )
)
